# shock_dyno.net
KiCad netlist of a schematic drawn in EAGLE
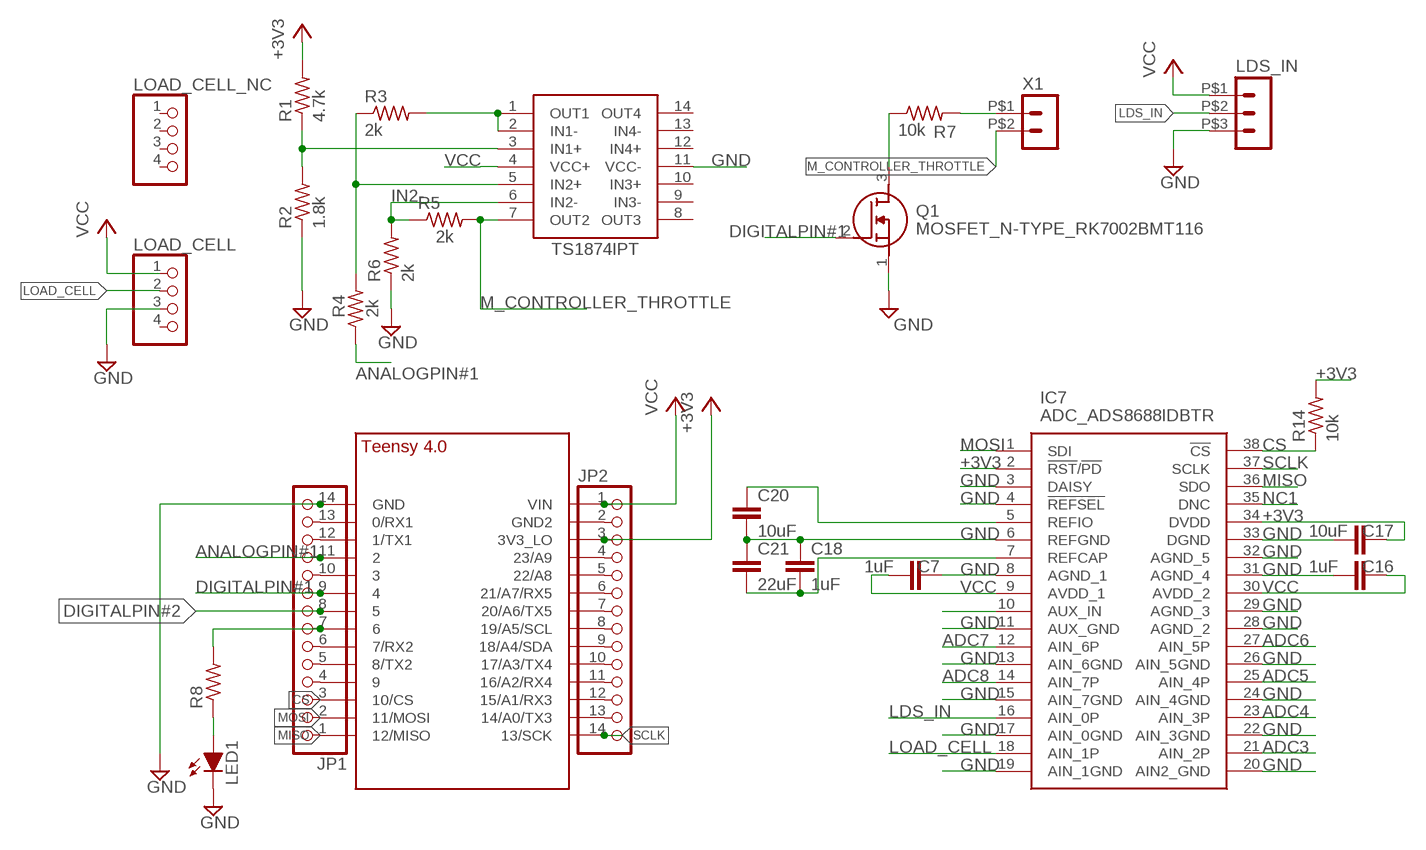
[diagram p0: schematic, sheet 1]

(export (version "E")
  (design (tool "Eeschema 10.0.6"))
  (components
    (comp (ref "C7")
      (value "1uF")
      (footprint "eagle-import:C0603")
      (libsource (lib "eagle-import") (part "CAP_SMDC0603"))
    )
    (comp (ref "C16")
      (value "1uF")
      (footprint "eagle-import:C0603")
      (libsource (lib "eagle-import") (part "CAP_SMDC0603"))
    )
    (comp (ref "C17")
      (value "10uF")
      (footprint "eagle-import:C0603")
      (libsource (lib "eagle-import") (part "CAP_SMDC0603"))
    )
    (comp (ref "C18")
      (value "1uF")
      (footprint "eagle-import:C0603")
      (libsource (lib "eagle-import") (part "CAP_SMDC0603"))
    )
    (comp (ref "C20")
      (value "10uF")
      (footprint "eagle-import:C0805")
      (libsource (lib "eagle-import") (part "CAP_SMDC0805"))
    )
    (comp (ref "C21")
      (value "22uF")
      (footprint "eagle-import:C1210")
      (libsource (lib "eagle-import") (part "CAP_SMDC1210"))
    )
    (comp (ref "IC7")
      (value "ADC_ADS8688IDBTR")
      (footprint "eagle-import:SOP50P640X120-38N")
      (fields
        (field (name "ARROW_PART_NUMBER") "ADS8688IDBTR")
        (field (name "MOUSER_PART_NUMBER") "595-ADS8688IDBTR")
      )
      (libsource (lib "eagle-import") (part "ADC_ADS8688IDBTR"))
    )
    (comp (ref "JP1")
      (value "PINHD-1X14")
      (footprint "eagle-import:1X14")
      (libsource (lib "eagle-import") (part "PINHD-1X14"))
    )
    (comp (ref "JP2")
      (value "PINHD-1X14")
      (footprint "eagle-import:1X14")
      (libsource (lib "eagle-import") (part "PINHD-1X14"))
    )
    (comp (ref "LDS_IN")
      (value "HEADER_POS3_43650-0300")
      (footprint "eagle-import:43650-0300")
      (libsource (lib "eagle-import") (part "HEADER_POS3_?43650-0300"))
    )
    (comp (ref "LED1")
      (value "LED-5MM")
      (footprint "eagle-import:LED-5MM")
      (libsource (lib "eagle-import") (part "LED-5MM"))
    )
    (comp (ref "LOAD_CELL")
      (value "PINHD-1X4")
      (footprint "eagle-import:1X04")
      (libsource (lib "eagle-import") (part "PINHD-1X4"))
    )
    (comp (ref "LOAD_CELL_NC")
      (value "PINHD-1X4")
      (footprint "eagle-import:1X04")
      (libsource (lib "eagle-import") (part "PINHD-1X4"))
    )
    (comp (ref "Q1")
      (value "MOSFET_N-TYPE_RK7002BMT116")
      (footprint "eagle-import:BSS64AHZGT116")
      (fields
        (field (name "MANUFACTURER_PART_NUMBER") "RK7002BMT116")
        (field (name "MOUSER_PART_NUMBER") "755-RK7002BMT116")
      )
      (libsource (lib "eagle-import") (part "MOSFET_N-TYPE_RK7002BMT116"))
    )
    (comp (ref "R1")
      (value "4.7k")
      (footprint "eagle-import:R0603")
      (libsource (lib "eagle-import") (part "RES_SMDR0603"))
    )
    (comp (ref "R2")
      (value "1.8k")
      (footprint "eagle-import:R0603")
      (libsource (lib "eagle-import") (part "RES_SMDR0603"))
    )
    (comp (ref "R3")
      (value "2k")
      (footprint "eagle-import:R0603")
      (libsource (lib "eagle-import") (part "RES_SMDR0603"))
    )
    (comp (ref "R4")
      (value "2k")
      (footprint "eagle-import:R0603")
      (libsource (lib "eagle-import") (part "RES_SMDR0603"))
    )
    (comp (ref "R5")
      (value "2k")
      (footprint "eagle-import:R0603")
      (libsource (lib "eagle-import") (part "RES_SMDR0603"))
    )
    (comp (ref "R6")
      (value "2k")
      (footprint "eagle-import:R0603")
      (libsource (lib "eagle-import") (part "RES_SMDR0603"))
    )
    (comp (ref "R7")
      (value "10k")
      (footprint "eagle-import:R0603")
      (libsource (lib "eagle-import") (part "RES_SMDR0603"))
    )
    (comp (ref "R8")
      (value "RES_SMDR0603")
      (footprint "eagle-import:R0603")
      (libsource (lib "eagle-import") (part "RES_SMDR0603"))
    )
    (comp (ref "R14")
      (value "10k")
      (footprint "eagle-import:R0603")
      (libsource (lib "eagle-import") (part "RES_SMDR0603"))
    )
    (comp (ref "U$1")
      (value "TS1874IPT")
      (footprint "eagle-import:TSSOP14")
      (libsource (lib "eagle-import") (part "TS1874IPT"))
    )
    (comp (ref "U$2")
      (value "TEENSY_4.0_SIMPLE")
      (footprint "eagle-import:TEENSY_4.0_SIMPLE")
      (libsource (lib "eagle-import") (part "TEENSY_4.0_SIMPLE"))
    )
    (comp (ref "X1")
      (value "HEADER_POS2_43650-0200")
      (footprint "eagle-import:43650-0200")
      (libsource (lib "eagle-import") (part "HEADER_POS2_?43650-0200"))
    )
  )
  (nets
    (net (code "1") (name "+3V3") (class "Default")
      (node (ref "C17") (pin "1") (pinfunction "1_1") (pintype "passive"))
      (node (ref "IC7") (pin "2") (pinfunction "~{RST}/~{PD}_2") (pintype "bidirectional"))
      (node (ref "IC7") (pin "34") (pinfunction "DVDD_34") (pintype "bidirectional"))
      (node (ref "JP2") (pin "3") (pinfunction "3_3") (pintype "passive"))
      (node (ref "R1") (pin "2") (pinfunction "2_2") (pintype "passive"))
      (node (ref "R14") (pin "2") (pinfunction "2_2") (pintype "passive"))
      (node (ref "U$2") (pin "3V3_LO") (pinfunction "3V3_LO_3V3_LO") (pintype "bidirectional"))
    )
    (net (code "2") (name "/ADC3") (class "Default")
      (node (ref "IC7") (pin "21") (pinfunction "AIN_2P_21") (pintype "bidirectional"))
    )
    (net (code "3") (name "/ADC4") (class "Default")
      (node (ref "IC7") (pin "23") (pinfunction "AIN_3P_23") (pintype "bidirectional"))
    )
    (net (code "4") (name "/ADC5") (class "Default")
      (node (ref "IC7") (pin "25") (pinfunction "AIN_4P_25") (pintype "bidirectional"))
    )
    (net (code "5") (name "/ADC6") (class "Default")
      (node (ref "IC7") (pin "27") (pinfunction "AIN_5P_27") (pintype "bidirectional"))
    )
    (net (code "6") (name "/ADC7") (class "Default")
      (node (ref "IC7") (pin "12") (pinfunction "AIN_6P_12") (pintype "bidirectional"))
    )
    (net (code "7") (name "/ADC8") (class "Default")
      (node (ref "IC7") (pin "14") (pinfunction "AIN_7P_14") (pintype "bidirectional"))
    )
    (net (code "8") (name "/ANALOGPIN#1") (class "Default")
      (node (ref "JP1") (pin "11") (pinfunction "11_11") (pintype "passive"))
      (node (ref "R4") (pin "1") (pinfunction "1_1") (pintype "passive"))
      (node (ref "U$2") (pin "2") (pinfunction "2_2") (pintype "bidirectional"))
    )
    (net (code "9") (name "/DIGITALPIN#1") (class "Default")
      (node (ref "JP1") (pin "9") (pinfunction "9_9") (pintype "passive"))
      (node (ref "Q1") (pin "2") (pinfunction "G_2") (pintype "bidirectional"))
      (node (ref "U$2") (pin "4/CANRX") (pinfunction "4_4/CANRX") (pintype "bidirectional"))
    )
    (net (code "10") (name "/IN2-") (class "Default")
      (node (ref "R5") (pin "1") (pinfunction "1_1") (pintype "passive"))
      (node (ref "R6") (pin "2") (pinfunction "2_2") (pintype "passive"))
      (node (ref "U$1") (pin "6") (pinfunction "IN2-_6") (pintype "bidirectional"))
    )
    (net (code "11") (name "/NC1") (class "Default")
      (node (ref "IC7") (pin "35") (pinfunction "DNC_35") (pintype "bidirectional"))
    )
    (net (code "12") (name "CS") (class "Default")
      (node (ref "IC7") (pin "38") (pinfunction "~{CS}_38") (pintype "bidirectional"))
      (node (ref "JP1") (pin "3") (pinfunction "3_3") (pintype "passive"))
      (node (ref "R14") (pin "1") (pinfunction "1_1") (pintype "passive"))
      (node (ref "U$2") (pin "10/CS") (pinfunction "10/CS_10/CS") (pintype "bidirectional"))
    )
    (net (code "13") (name "DIGITALPIN#2") (class "Default")
      (node (ref "JP1") (pin "8") (pinfunction "8_8") (pintype "passive"))
      (node (ref "U$2") (pin "5") (pinfunction "5_5") (pintype "bidirectional"))
    )
    (net (code "14") (name "GND") (class "Default")
      (node (ref "C16") (pin "2") (pinfunction "2_2") (pintype "passive"))
      (node (ref "C17") (pin "2") (pinfunction "2_2") (pintype "passive"))
      (node (ref "C18") (pin "1") (pinfunction "1_1") (pintype "passive"))
      (node (ref "C20") (pin "2") (pinfunction "2_2") (pintype "passive"))
      (node (ref "C21") (pin "1") (pinfunction "1_1") (pintype "passive"))
      (node (ref "C7") (pin "1") (pinfunction "1_1") (pintype "passive"))
      (node (ref "IC7") (pin "11") (pinfunction "AUX_GND_11") (pintype "bidirectional"))
      (node (ref "IC7") (pin "13") (pinfunction "AIN_6GND_13") (pintype "bidirectional"))
      (node (ref "IC7") (pin "15") (pinfunction "AIN_7GND_15") (pintype "bidirectional"))
      (node (ref "IC7") (pin "17") (pinfunction "AIN_0GND_17") (pintype "bidirectional"))
      (node (ref "IC7") (pin "19") (pinfunction "AIN_1GND_19") (pintype "bidirectional"))
      (node (ref "IC7") (pin "20") (pinfunction "AIN2_GND_20") (pintype "bidirectional"))
      (node (ref "IC7") (pin "22") (pinfunction "AIN_3GND_22") (pintype "bidirectional"))
      (node (ref "IC7") (pin "24") (pinfunction "AIN_4GND_24") (pintype "bidirectional"))
      (node (ref "IC7") (pin "26") (pinfunction "AIN_5GND_26") (pintype "bidirectional"))
      (node (ref "IC7") (pin "28") (pinfunction "AGND_2_28") (pintype "bidirectional"))
      (node (ref "IC7") (pin "29") (pinfunction "AGND_3_29") (pintype "bidirectional"))
      (node (ref "IC7") (pin "3") (pinfunction "DAISY_3") (pintype "bidirectional"))
      (node (ref "IC7") (pin "31") (pinfunction "AGND_4_31") (pintype "bidirectional"))
      (node (ref "IC7") (pin "32") (pinfunction "AGND_5_32") (pintype "bidirectional"))
      (node (ref "IC7") (pin "33") (pinfunction "DGND_33") (pintype "bidirectional"))
      (node (ref "IC7") (pin "4") (pinfunction "~{REFSEL}_4") (pintype "bidirectional"))
      (node (ref "IC7") (pin "6") (pinfunction "REFGND_6") (pintype "bidirectional"))
      (node (ref "IC7") (pin "8") (pinfunction "AGND_1_8") (pintype "bidirectional"))
      (node (ref "JP1") (pin "14") (pinfunction "14_14") (pintype "passive"))
      (node (ref "LDS_IN") (pin "P$3") (pinfunction "3_P$3") (pintype "passive"))
      (node (ref "LED1") (pin "K") (pinfunction "C_K") (pintype "passive"))
      (node (ref "LOAD_CELL") (pin "3") (pinfunction "3_3") (pintype "passive"))
      (node (ref "Q1") (pin "1") (pinfunction "S_1") (pintype "bidirectional"))
      (node (ref "R2") (pin "1") (pinfunction "1_1") (pintype "passive"))
      (node (ref "R6") (pin "1") (pinfunction "1_1") (pintype "passive"))
      (node (ref "U$1") (pin "11") (pinfunction "VCC-_11") (pintype "bidirectional"))
      (node (ref "U$2") (pin "GND") (pinfunction "GND_GND") (pintype "bidirectional"))
    )
    (net (code "15") (name "LDS_IN") (class "Default")
      (node (ref "IC7") (pin "16") (pinfunction "AIN_0P_16") (pintype "bidirectional"))
      (node (ref "LDS_IN") (pin "P$2") (pinfunction "2_P$2") (pintype "passive"))
    )
    (net (code "16") (name "LOAD_CELL") (class "Default")
      (node (ref "IC7") (pin "18") (pinfunction "AIN_1P_18") (pintype "bidirectional"))
      (node (ref "LOAD_CELL") (pin "2") (pinfunction "2_2") (pintype "passive"))
    )
    (net (code "17") (name "MISO") (class "Default")
      (node (ref "IC7") (pin "36") (pinfunction "SDO_36") (pintype "bidirectional"))
      (node (ref "JP1") (pin "1") (pinfunction "1_1") (pintype "passive"))
      (node (ref "U$2") (pin "12/MISO") (pinfunction "12/MISO_12/MISO") (pintype "bidirectional"))
    )
    (net (code "18") (name "MOSI") (class "Default")
      (node (ref "IC7") (pin "1") (pinfunction "SDI_1") (pintype "bidirectional"))
      (node (ref "JP1") (pin "2") (pinfunction "2_2") (pintype "passive"))
      (node (ref "U$2") (pin "11/MOSI") (pinfunction "11/MOSI_11/MOSI") (pintype "bidirectional"))
    )
    (net (code "19") (name "M_CONTROLLER_THROTTLE") (class "Default")
      (node (ref "R5") (pin "2") (pinfunction "2_2") (pintype "passive"))
      (node (ref "U$1") (pin "7") (pinfunction "OUT2_7") (pintype "bidirectional"))
      (node (ref "X1") (pin "P$2") (pinfunction "2_P$2") (pintype "passive"))
    )
    (net (code "20") (name "Net-(IC7-REFCAP)") (class "Default")
      (node (ref "C18") (pin "2") (pinfunction "2_2") (pintype "passive"))
      (node (ref "C21") (pin "2") (pinfunction "2_2") (pintype "passive"))
      (node (ref "IC7") (pin "7") (pinfunction "REFCAP_7") (pintype "bidirectional"))
    )
    (net (code "21") (name "Net-(IC7-REFIO)") (class "Default")
      (node (ref "C20") (pin "1") (pinfunction "1_1") (pintype "passive"))
      (node (ref "IC7") (pin "5") (pinfunction "REFIO_5") (pintype "bidirectional"))
    )
    (net (code "22") (name "Net-(JP1-Pad7)") (class "Default")
      (node (ref "JP1") (pin "7") (pinfunction "7_7") (pintype "passive"))
      (node (ref "R8") (pin "2") (pinfunction "2_2") (pintype "passive"))
      (node (ref "U$2") (pin "6") (pinfunction "6_6") (pintype "bidirectional"))
    )
    (net (code "23") (name "Net-(JP2-Pad2)") (class "Default")
      (node (ref "JP2") (pin "2") (pinfunction "2_2") (pintype "passive"))
      (node (ref "U$2") (pin "GND2") (pinfunction "GND2_GND2") (pintype "bidirectional"))
    )
    (net (code "24") (name "Net-(JP2-Pad4)") (class "Default")
      (node (ref "JP2") (pin "4") (pinfunction "4_4") (pintype "passive"))
      (node (ref "U$2") (pin "23/A9") (pinfunction "23/A9_23/A9") (pintype "bidirectional"))
    )
    (net (code "25") (name "Net-(JP2-Pad5)") (class "Default")
      (node (ref "JP2") (pin "5") (pinfunction "5_5") (pintype "passive"))
      (node (ref "U$2") (pin "22/A8") (pinfunction "22/A8_22/A8") (pintype "bidirectional"))
    )
    (net (code "26") (name "Net-(JP2-Pad8)") (class "Default")
      (node (ref "JP2") (pin "8") (pinfunction "8_8") (pintype "passive"))
      (node (ref "U$2") (pin "19/A5/SCL") (pinfunction "19/A5/SCL_19/A5/SCL") (pintype "bidirectional"))
    )
    (net (code "27") (name "Net-(JP2-Pad9)") (class "Default")
      (node (ref "JP2") (pin "9") (pinfunction "9_9") (pintype "passive"))
      (node (ref "U$2") (pin "18/A4/SDA") (pinfunction "18/A4/SDA_18/A4/SDA") (pintype "bidirectional"))
    )
    (net (code "28") (name "Net-(LED1-PadA)") (class "Default")
      (node (ref "LED1") (pin "A") (pinfunction "A_A") (pintype "passive"))
      (node (ref "R8") (pin "1") (pinfunction "1_1") (pintype "passive"))
    )
    (net (code "29") (name "Net-(Q1-D)") (class "Default")
      (node (ref "Q1") (pin "3") (pinfunction "D_3") (pintype "bidirectional"))
      (node (ref "R7") (pin "1") (pinfunction "1_1") (pintype "passive"))
    )
    (net (code "30") (name "Net-(U$1-IN1+)") (class "Default")
      (node (ref "R1") (pin "1") (pinfunction "1_1") (pintype "passive"))
      (node (ref "R2") (pin "2") (pinfunction "2_2") (pintype "passive"))
      (node (ref "U$1") (pin "3") (pinfunction "IN1+_3") (pintype "bidirectional"))
    )
    (net (code "31") (name "Net-(U$1-IN1-)") (class "Default")
      (node (ref "R3") (pin "2") (pinfunction "2_2") (pintype "passive"))
      (node (ref "U$1") (pin "1") (pinfunction "OUT1_1") (pintype "bidirectional"))
      (node (ref "U$1") (pin "2") (pinfunction "IN1-_2") (pintype "bidirectional"))
    )
    (net (code "32") (name "Net-(U$1-IN2+)") (class "Default")
      (node (ref "R3") (pin "1") (pinfunction "1_1") (pintype "passive"))
      (node (ref "R4") (pin "2") (pinfunction "2_2") (pintype "passive"))
      (node (ref "U$1") (pin "5") (pinfunction "IN2+_5") (pintype "bidirectional"))
    )
    (net (code "33") (name "Net-(U$2-0{slash}RX1)") (class "Default")
      (node (ref "JP1") (pin "13") (pinfunction "13_13") (pintype "passive"))
      (node (ref "U$2") (pin "0/RX") (pinfunction "0/RX1_0/RX") (pintype "bidirectional"))
    )
    (net (code "34") (name "Net-(U$2-1{slash}TX1)") (class "Default")
      (node (ref "JP1") (pin "12") (pinfunction "12_12") (pintype "passive"))
      (node (ref "U$2") (pin "1/TX") (pinfunction "1/TX1_1/TX") (pintype "bidirectional"))
    )
    (net (code "35") (name "Net-(U$2-3)") (class "Default")
      (node (ref "JP1") (pin "10") (pinfunction "10_10") (pintype "passive"))
      (node (ref "U$2") (pin "3/CANTX") (pinfunction "3_3/CANTX") (pintype "bidirectional"))
    )
    (net (code "36") (name "Net-(U$2-7{slash}RX2)") (class "Default")
      (node (ref "JP1") (pin "6") (pinfunction "6_6") (pintype "passive"))
      (node (ref "U$2") (pin "7") (pinfunction "7/RX2_7") (pintype "bidirectional"))
    )
    (net (code "37") (name "Net-(U$2-8{slash}TX2)") (class "Default")
      (node (ref "JP1") (pin "5") (pinfunction "5_5") (pintype "passive"))
      (node (ref "U$2") (pin "8") (pinfunction "8/TX2_8") (pintype "bidirectional"))
    )
    (net (code "38") (name "Net-(U$2-9)") (class "Default")
      (node (ref "JP1") (pin "4") (pinfunction "4_4") (pintype "passive"))
      (node (ref "U$2") (pin "9/CS") (pinfunction "9_9/CS") (pintype "bidirectional"))
    )
    (net (code "39") (name "Net-(U$2-14{slash}A0{slash}TX3)") (class "Default")
      (node (ref "JP2") (pin "13") (pinfunction "13_13") (pintype "passive"))
      (node (ref "U$2") (pin "14/A0") (pinfunction "14/A0/TX3_14/A0") (pintype "bidirectional"))
    )
    (net (code "40") (name "Net-(U$2-15{slash}A1{slash}RX3)") (class "Default")
      (node (ref "JP2") (pin "12") (pinfunction "12_12") (pintype "passive"))
      (node (ref "U$2") (pin "15/A1") (pinfunction "15/A1/RX3_15/A1") (pintype "bidirectional"))
    )
    (net (code "41") (name "Net-(U$2-16{slash}A2{slash}RX4)") (class "Default")
      (node (ref "JP2") (pin "11") (pinfunction "11_11") (pintype "passive"))
      (node (ref "U$2") (pin "16/A2") (pinfunction "16/A2/RX4_16/A2") (pintype "bidirectional"))
    )
    (net (code "42") (name "Net-(U$2-17{slash}A3{slash}TX4)") (class "Default")
      (node (ref "JP2") (pin "10") (pinfunction "10_10") (pintype "passive"))
      (node (ref "U$2") (pin "17/A3") (pinfunction "17/A3/TX4_17/A3") (pintype "bidirectional"))
    )
    (net (code "43") (name "Net-(U$2-20{slash}A6{slash}TX5)") (class "Default")
      (node (ref "JP2") (pin "7") (pinfunction "7_7") (pintype "passive"))
      (node (ref "U$2") (pin "20/A6") (pinfunction "20/A6/TX5_20/A6") (pintype "bidirectional"))
    )
    (net (code "44") (name "Net-(U$2-21{slash}A7{slash}RX5)") (class "Default")
      (node (ref "JP2") (pin "6") (pinfunction "6_6") (pintype "passive"))
      (node (ref "U$2") (pin "21/A7") (pinfunction "21/A7/RX5_21/A7") (pintype "bidirectional"))
    )
    (net (code "45") (name "Net-(X1-1)") (class "Default")
      (node (ref "R7") (pin "2") (pinfunction "2_2") (pintype "passive"))
      (node (ref "X1") (pin "P$1") (pinfunction "1_P$1") (pintype "passive"))
    )
    (net (code "46") (name "SCLK") (class "Default")
      (node (ref "IC7") (pin "37") (pinfunction "SCLK_37") (pintype "bidirectional"))
      (node (ref "JP2") (pin "14") (pinfunction "14_14") (pintype "passive"))
      (node (ref "U$2") (pin "13/SCK") (pinfunction "13/SCK_13/SCK") (pintype "bidirectional"))
    )
    (net (code "47") (name "VCC") (class "Default")
      (node (ref "C16") (pin "1") (pinfunction "1_1") (pintype "passive"))
      (node (ref "C7") (pin "2") (pinfunction "2_2") (pintype "passive"))
      (node (ref "IC7") (pin "30") (pinfunction "AVDD_2_30") (pintype "bidirectional"))
      (node (ref "IC7") (pin "9") (pinfunction "AVDD_1_9") (pintype "bidirectional"))
      (node (ref "JP2") (pin "1") (pinfunction "1_1") (pintype "passive"))
      (node (ref "LDS_IN") (pin "P$1") (pinfunction "1_P$1") (pintype "passive"))
      (node (ref "LOAD_CELL") (pin "1") (pinfunction "1_1") (pintype "passive"))
      (node (ref "U$1") (pin "4") (pinfunction "VCC+_4") (pintype "bidirectional"))
      (node (ref "U$2") (pin "VIN") (pinfunction "VIN_VIN") (pintype "bidirectional"))
    )
    (net (code "48") (name "unconnected-(IC7-AUX_IN-Pad10)") (class "Default")
      (node (ref "IC7") (pin "10") (pinfunction "AUX_IN_10") (pintype "bidirectional"))
    )
    (net (code "49") (name "unconnected-(LOAD_CELL-Pad4)") (class "Default")
      (node (ref "LOAD_CELL") (pin "4") (pinfunction "4_4") (pintype "passive"))
    )
    (net (code "50") (name "unconnected-(LOAD_CELL_NC-Pad1)") (class "Default")
      (node (ref "LOAD_CELL_NC") (pin "1") (pinfunction "1_1") (pintype "passive"))
    )
    (net (code "51") (name "unconnected-(LOAD_CELL_NC-Pad2)") (class "Default")
      (node (ref "LOAD_CELL_NC") (pin "2") (pinfunction "2_2") (pintype "passive"))
    )
    (net (code "52") (name "unconnected-(LOAD_CELL_NC-Pad3)") (class "Default")
      (node (ref "LOAD_CELL_NC") (pin "3") (pinfunction "3_3") (pintype "passive"))
    )
    (net (code "53") (name "unconnected-(LOAD_CELL_NC-Pad4)") (class "Default")
      (node (ref "LOAD_CELL_NC") (pin "4") (pinfunction "4_4") (pintype "passive"))
    )
    (net (code "54") (name "unconnected-(U$1-IN3+-Pad10)") (class "Default")
      (node (ref "U$1") (pin "10") (pinfunction "IN3+_10") (pintype "bidirectional"))
    )
    (net (code "55") (name "unconnected-(U$1-IN3--Pad9)") (class "Default")
      (node (ref "U$1") (pin "9") (pinfunction "IN3-_9") (pintype "bidirectional"))
    )
    (net (code "56") (name "unconnected-(U$1-IN4+-Pad12)") (class "Default")
      (node (ref "U$1") (pin "12") (pinfunction "IN4+_12") (pintype "bidirectional"))
    )
    (net (code "57") (name "unconnected-(U$1-IN4--Pad13)") (class "Default")
      (node (ref "U$1") (pin "13") (pinfunction "IN4-_13") (pintype "bidirectional"))
    )
    (net (code "58") (name "unconnected-(U$1-OUT3-Pad8)") (class "Default")
      (node (ref "U$1") (pin "8") (pinfunction "OUT3_8") (pintype "bidirectional"))
    )
    (net (code "59") (name "unconnected-(U$1-OUT4-Pad14)") (class "Default")
      (node (ref "U$1") (pin "14") (pinfunction "OUT4_14") (pintype "bidirectional"))
    )
  )
)
